# Control_Logic.net
KiCad netlist of a schematic drawn in EAGLE
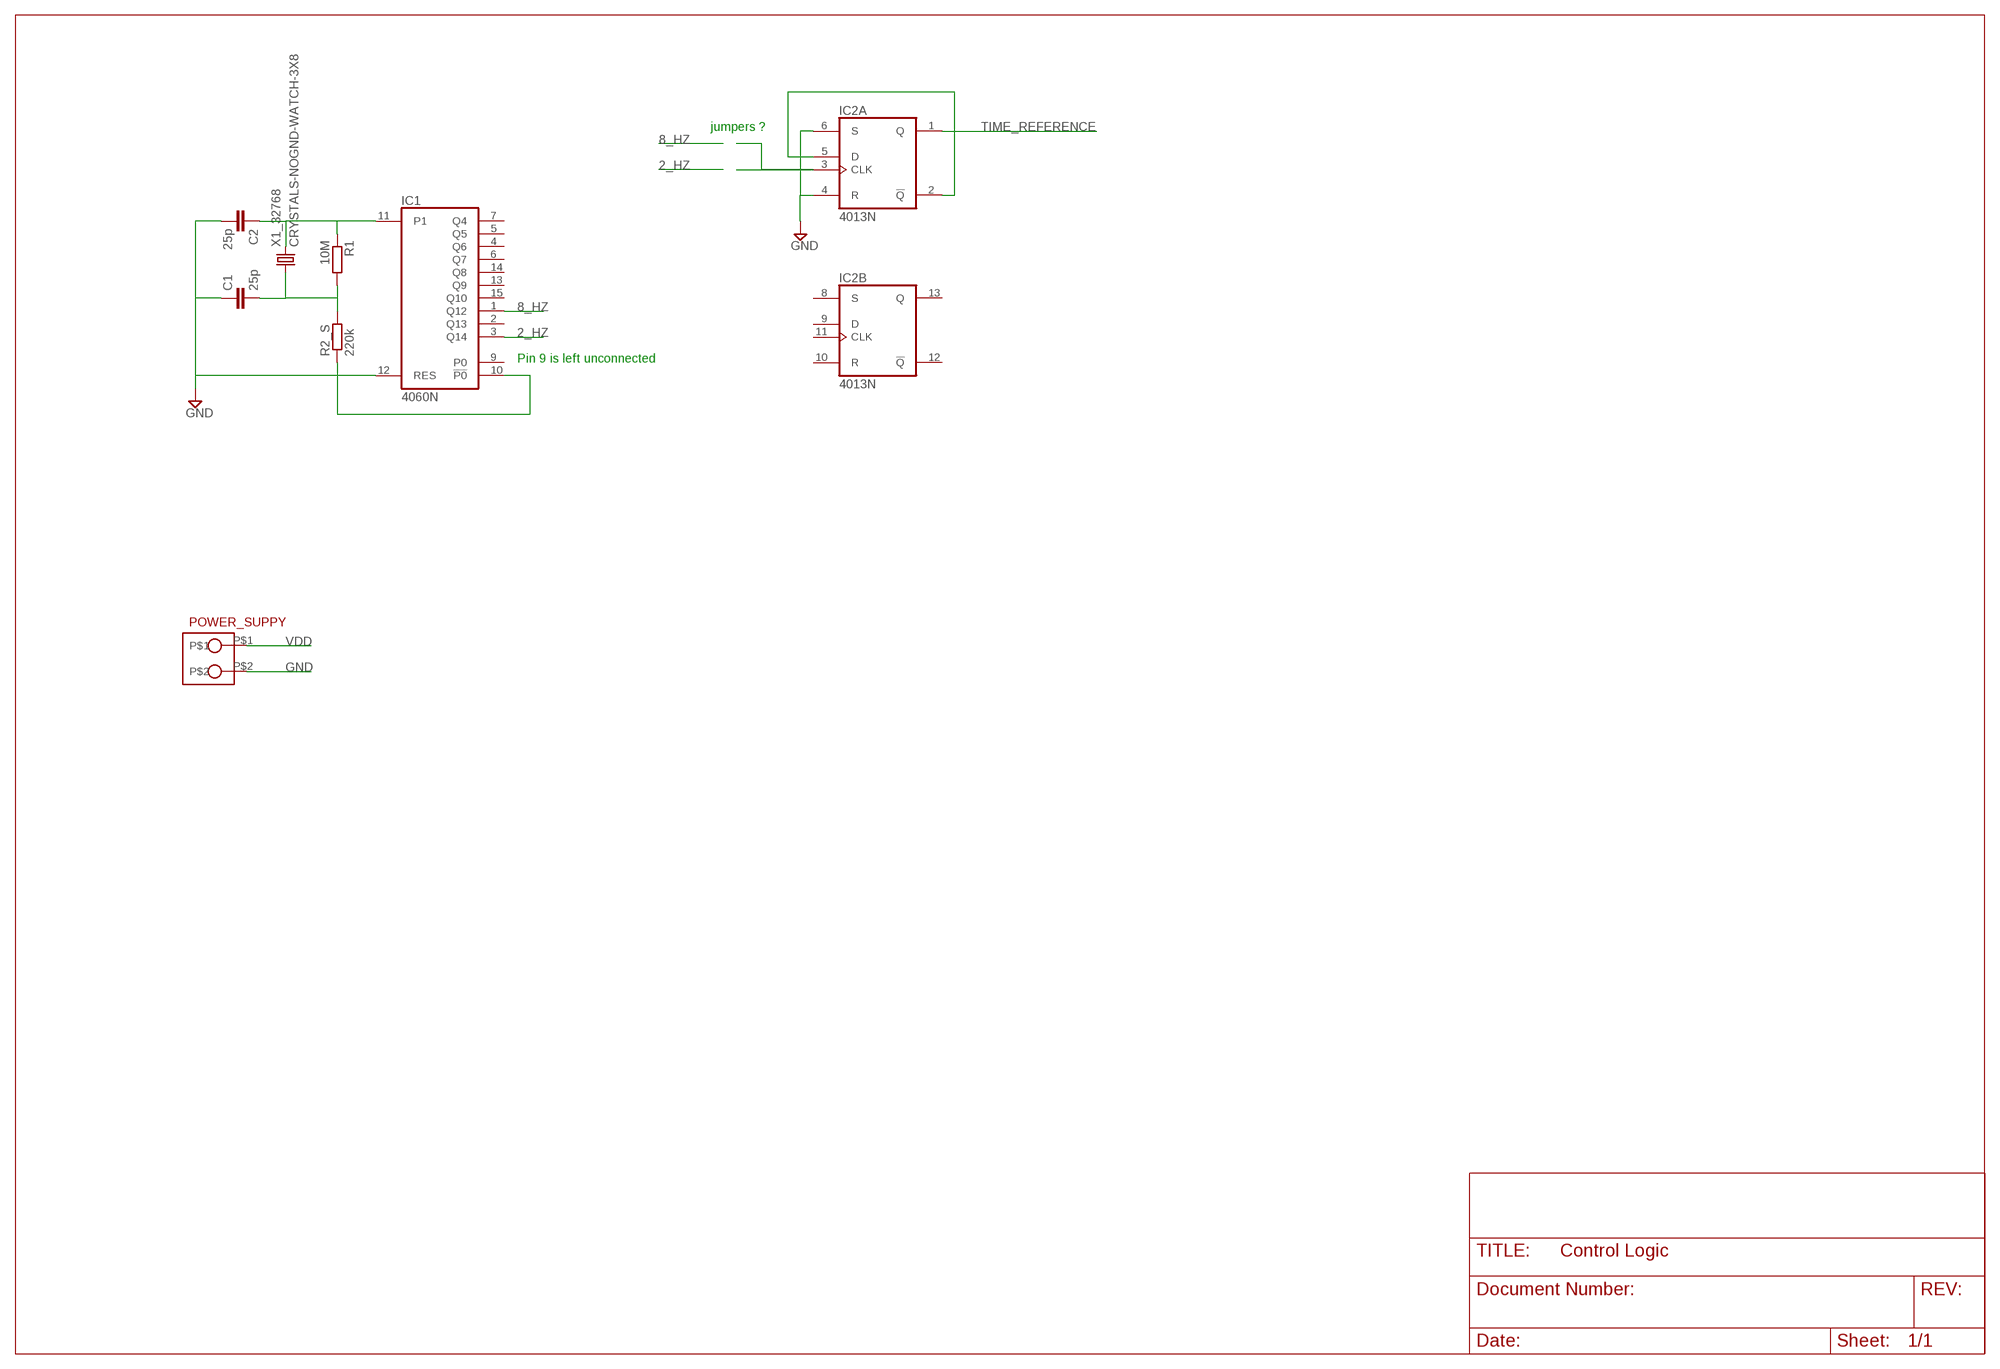
[diagram p0: schematic, sheet 1]

(export (version "E")
  (design (tool "Eeschema 10.0.6"))
  (components
    (comp (ref "C1")
      (value "25p")
      (footprint "eagle-import:C050-025X075")
      (libsource (lib "eagle-import") (part "C-EU050-025X075"))
    )
    (comp (ref "C2")
      (value "25p")
      (footprint "eagle-import:C050-025X075")
      (libsource (lib "eagle-import") (part "C-EU050-025X075"))
    )
    (comp (ref "IC1")
      (value "4060N")
      (footprint "eagle-import:DIL16")
      (libsource (lib "eagle-import") (part "4060N"))
    )
    (comp (ref "IC2")
      (value "4013N")
      (footprint "eagle-import:DIL14")
      (libsource (lib "eagle-import") (part "4013N"))
    )
    (comp (ref "POWER_SUPPY")
      (value "CON_2_SIL")
      (footprint "eagle-import:SIL_2_0.2INCH")
      (libsource (lib "eagle-import") (part "CON_2_SIL"))
    )
    (comp (ref "R1")
      (value "10M")
      (footprint "eagle-import:0207_10")
      (libsource (lib "eagle-import") (part "R-EU_0207/10"))
    )
    (comp (ref "R2_S")
      (value "220k")
      (footprint "eagle-import:0207_10")
      (libsource (lib "eagle-import") (part "R-EU_0207/10"))
    )
    (comp (ref "X1_32768")
      (value "CRYSTALS-NOGND-WATCH-3X8")
      (footprint "eagle-import:WATCH-3X8")
      (libsource (lib "eagle-import") (part "CRYSTALS-NOGND-WATCH-3X8"))
    )
  )
  (nets
    (net (code "1") (name "/2_HZ") (class "Default")
      (node (ref "IC1") (pin "3") (pinfunction "Q14_3") (pintype "output"))
    )
    (net (code "2") (name "/8_HZ") (class "Default")
      (node (ref "IC1") (pin "1") (pinfunction "Q12_1") (pintype "output"))
    )
    (net (code "3") (name "/TIME_REFERENCE") (class "Default")
      (node (ref "IC2") (pin "1") (pinfunction "Q_1") (pintype "output"))
    )
    (net (code "4") (name "/VDD") (class "Default")
      (node (ref "POWER_SUPPY") (pin "P$1") (pinfunction "P$1_P$1") (pintype "bidirectional"))
    )
    (net (code "5") (name "GND") (class "Default")
      (node (ref "C1") (pin "1") (pinfunction "1_1") (pintype "passive"))
      (node (ref "C2") (pin "2") (pinfunction "2_2") (pintype "passive"))
      (node (ref "IC1") (pin "12") (pinfunction "RES_12") (pintype "input"))
      (node (ref "IC2") (pin "4") (pinfunction "R_4") (pintype "input"))
      (node (ref "IC2") (pin "6") (pinfunction "S_6") (pintype "input"))
      (node (ref "POWER_SUPPY") (pin "P$2") (pinfunction "P$2_P$2") (pintype "bidirectional"))
    )
    (net (code "6") (name "Net-(C1-Pad2)") (class "Default")
      (node (ref "C1") (pin "2") (pinfunction "2_2") (pintype "passive"))
      (node (ref "R1") (pin "2") (pinfunction "2_2") (pintype "passive"))
      (node (ref "R2_S") (pin "2") (pinfunction "2_2") (pintype "passive"))
      (node (ref "X1_32768") (pin "1") (pinfunction "1_1") (pintype "passive"))
    )
    (net (code "7") (name "Net-(IC1A-P1)") (class "Default")
      (node (ref "C2") (pin "1") (pinfunction "1_1") (pintype "passive"))
      (node (ref "IC1") (pin "11") (pinfunction "P1_11") (pintype "input"))
      (node (ref "R1") (pin "1") (pinfunction "1_1") (pintype "passive"))
      (node (ref "X1_32768") (pin "2") (pinfunction "2_2") (pintype "passive"))
    )
    (net (code "8") (name "Net-(IC1A-~{P0})") (class "Default")
      (node (ref "IC1") (pin "10") (pinfunction "~{P0}_10") (pintype "output"))
      (node (ref "R2_S") (pin "1") (pinfunction "1_1") (pintype "passive"))
    )
    (net (code "9") (name "Net-(IC2A-D)") (class "Default")
      (node (ref "IC2") (pin "2") (pinfunction "~{Q}_2") (pintype "output"))
      (node (ref "IC2") (pin "5") (pinfunction "D_5") (pintype "input"))
    )
    (net (code "10") (name "unconnected-(IC1A-P0-Pad9)") (class "Default")
      (node (ref "IC1") (pin "9") (pinfunction "P0_9") (pintype "output"))
    )
    (net (code "11") (name "unconnected-(IC1A-Q4-Pad7)") (class "Default")
      (node (ref "IC1") (pin "7") (pinfunction "Q4_7") (pintype "output"))
    )
    (net (code "12") (name "unconnected-(IC1A-Q5-Pad5)") (class "Default")
      (node (ref "IC1") (pin "5") (pinfunction "Q5_5") (pintype "output"))
    )
    (net (code "13") (name "unconnected-(IC1A-Q6-Pad4)") (class "Default")
      (node (ref "IC1") (pin "4") (pinfunction "Q6_4") (pintype "output"))
    )
    (net (code "14") (name "unconnected-(IC1A-Q7-Pad6)") (class "Default")
      (node (ref "IC1") (pin "6") (pinfunction "Q7_6") (pintype "output"))
    )
    (net (code "15") (name "unconnected-(IC1A-Q8-Pad14)") (class "Default")
      (node (ref "IC1") (pin "14") (pinfunction "Q8_14") (pintype "output"))
    )
    (net (code "16") (name "unconnected-(IC1A-Q9-Pad13)") (class "Default")
      (node (ref "IC1") (pin "13") (pinfunction "Q9_13") (pintype "output"))
    )
    (net (code "17") (name "unconnected-(IC1A-Q10-Pad15)") (class "Default")
      (node (ref "IC1") (pin "15") (pinfunction "Q10_15") (pintype "output"))
    )
    (net (code "18") (name "unconnected-(IC1A-Q13-Pad2)") (class "Default")
      (node (ref "IC1") (pin "2") (pinfunction "Q13_2") (pintype "output"))
    )
    (net (code "19") (name "unconnected-(IC2A-CLK-Pad3)") (class "Default")
      (node (ref "IC2") (pin "3") (pinfunction "CLK_3") (pintype "input"))
    )
    (net (code "20") (name "unconnected-(IC2B-CLK-Pad11)") (class "Default")
      (node (ref "IC2") (pin "11") (pinfunction "CLK_11") (pintype "input"))
    )
    (net (code "21") (name "unconnected-(IC2B-D-Pad9)") (class "Default")
      (node (ref "IC2") (pin "9") (pinfunction "D_9") (pintype "input"))
    )
    (net (code "22") (name "unconnected-(IC2B-Q-Pad13)") (class "Default")
      (node (ref "IC2") (pin "13") (pinfunction "Q_13") (pintype "output"))
    )
    (net (code "23") (name "unconnected-(IC2B-R-Pad10)") (class "Default")
      (node (ref "IC2") (pin "10") (pinfunction "R_10") (pintype "input"))
    )
    (net (code "24") (name "unconnected-(IC2B-S-Pad8)") (class "Default")
      (node (ref "IC2") (pin "8") (pinfunction "S_8") (pintype "input"))
    )
    (net (code "25") (name "unconnected-(IC2B-~{Q}-Pad12)") (class "Default")
      (node (ref "IC2") (pin "12") (pinfunction "~{Q}_12") (pintype "output"))
    )
  )
)
